# 6612.net
KiCad netlist of a schematic drawn in Altium Designer
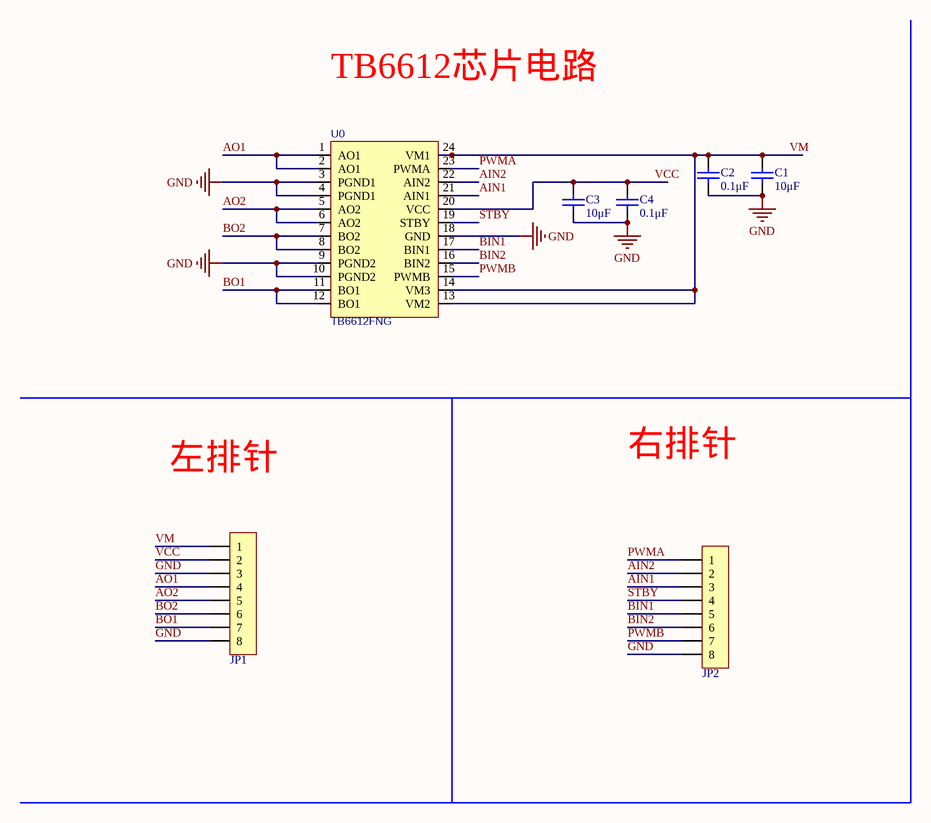
[diagram p0: 6612.SchDoc]

(export (version "E")
  (design (tool "Eeschema 10.0.6"))
  (components
    (comp (ref "C1")
      (value "10μF")
      (footprint "C0805_L")
      (description "贴片电容/MLCC电容")
      (libsource (lib "0.1 - 电阻-电容-电感-晶振-晶体-磁珠-电位器-法拉电容-馈通电容") (part "C"))
    )
    (comp (ref "C2")
      (value "0.1μF")
      (footprint "C0805_L")
      (description "贴片电容/MLCC电容")
      (libsource (lib "0.1 - 电阻-电容-电感-晶振-晶体-磁珠-电位器-法拉电容-馈通电容") (part "C"))
    )
    (comp (ref "C3")
      (value "10μF")
      (footprint "C0805_L")
      (description "贴片电容/MLCC电容")
      (libsource (lib "0.1 - 电阻-电容-电感-晶振-晶体-磁珠-电位器-法拉电容-馈通电容") (part "C"))
    )
    (comp (ref "C4")
      (value "0.1μF")
      (footprint "C0805_L")
      (description "贴片电容/MLCC电容")
      (libsource (lib "0.1 - 电阻-电容-电感-晶振-晶体-磁珠-电位器-法拉电容-馈通电容") (part "C"))
    )
    (comp (ref "JP1")
      (value "HDR-1X8")
      (footprint "HDR2.54-LI-8P")
      (description "8P接插件")
      (libsource (lib "5.5 - 2.54mm连接器(KF2EDGK_XH2.54_2.54排针排母)") (part "Header 8"))
    )
    (comp (ref "JP2")
      (value "HDR-1X8")
      (footprint "HDR2.54-LI-8P")
      (description "8P接插件")
      (libsource (lib "5.5 - 2.54mm连接器(KF2EDGK_XH2.54_2.54排针排母)") (part "Header 8"))
    )
    (comp (ref "U0")
      (value "TB6612FNG")
      (footprint "SSOP24_M")
      (description "电机驱动")
      (libsource (lib "0.8 - 常见芯片") (part "TB6612FNG"))
    )
  )
  (nets
    (net (code "1") (name "/AIN1") (class "Default")
      (node (ref "JP2") (pin "3") (pinfunction "3_3") (pintype "passive"))
      (node (ref "U0") (pin "21") (pinfunction "AIN1_21") (pintype "passive"))
    )
    (net (code "2") (name "/AIN2") (class "Default")
      (node (ref "JP2") (pin "2") (pinfunction "2_2") (pintype "passive"))
      (node (ref "U0") (pin "22") (pinfunction "AIN2_22") (pintype "passive"))
    )
    (net (code "3") (name "/AO1") (class "Default")
      (node (ref "JP1") (pin "4") (pinfunction "4_4") (pintype "passive"))
      (node (ref "U0") (pin "1") (pinfunction "AO1_1") (pintype "passive"))
      (node (ref "U0") (pin "2") (pinfunction "AO1_2") (pintype "passive"))
    )
    (net (code "4") (name "/AO2") (class "Default")
      (node (ref "JP1") (pin "5") (pinfunction "5_5") (pintype "passive"))
      (node (ref "U0") (pin "5") (pinfunction "AO2_5") (pintype "passive"))
      (node (ref "U0") (pin "6") (pinfunction "AO2_6") (pintype "passive"))
    )
    (net (code "5") (name "/BIN1") (class "Default")
      (node (ref "JP2") (pin "5") (pinfunction "5_5") (pintype "passive"))
      (node (ref "U0") (pin "17") (pinfunction "BIN1_17") (pintype "passive"))
    )
    (net (code "6") (name "/BIN2") (class "Default")
      (node (ref "JP2") (pin "6") (pinfunction "6_6") (pintype "passive"))
      (node (ref "U0") (pin "16") (pinfunction "BIN2_16") (pintype "passive"))
    )
    (net (code "7") (name "/BO1") (class "Default")
      (node (ref "JP1") (pin "7") (pinfunction "7_7") (pintype "passive"))
      (node (ref "U0") (pin "11") (pinfunction "BO1_11") (pintype "passive"))
      (node (ref "U0") (pin "12") (pinfunction "BO1_12") (pintype "passive"))
    )
    (net (code "8") (name "/BO2") (class "Default")
      (node (ref "JP1") (pin "6") (pinfunction "6_6") (pintype "passive"))
      (node (ref "U0") (pin "7") (pinfunction "BO2_7") (pintype "passive"))
      (node (ref "U0") (pin "8") (pinfunction "BO2_8") (pintype "passive"))
    )
    (net (code "9") (name "/PWMA") (class "Default")
      (node (ref "JP2") (pin "1") (pinfunction "1_1") (pintype "passive"))
      (node (ref "U0") (pin "23") (pinfunction "PWMA_23") (pintype "passive"))
    )
    (net (code "10") (name "/PWMB") (class "Default")
      (node (ref "JP2") (pin "7") (pinfunction "7_7") (pintype "passive"))
      (node (ref "U0") (pin "15") (pinfunction "PWMB_15") (pintype "passive"))
    )
    (net (code "11") (name "/STBY") (class "Default")
      (node (ref "JP2") (pin "4") (pinfunction "4_4") (pintype "passive"))
      (node (ref "U0") (pin "19") (pinfunction "STBY_19") (pintype "passive"))
    )
    (net (code "12") (name "/VCC") (class "Default")
      (node (ref "C3") (pin "2") (pinfunction "2_2") (pintype "passive"))
      (node (ref "C4") (pin "2") (pinfunction "2_2") (pintype "passive"))
      (node (ref "JP1") (pin "2") (pinfunction "2_2") (pintype "passive"))
      (node (ref "U0") (pin "20") (pinfunction "VCC_20") (pintype "passive"))
    )
    (net (code "13") (name "/VM") (class "Default")
      (node (ref "C1") (pin "2") (pinfunction "2_2") (pintype "passive"))
      (node (ref "C2") (pin "2") (pinfunction "2_2") (pintype "passive"))
      (node (ref "JP1") (pin "1") (pinfunction "1_1") (pintype "passive"))
      (node (ref "U0") (pin "13") (pinfunction "VM2_13") (pintype "passive"))
      (node (ref "U0") (pin "14") (pinfunction "VM3_14") (pintype "passive"))
      (node (ref "U0") (pin "24") (pinfunction "VM1_24") (pintype "passive"))
    )
    (net (code "14") (name "GND") (class "Default")
      (node (ref "C1") (pin "1") (pinfunction "1_1") (pintype "passive"))
      (node (ref "C2") (pin "1") (pinfunction "1_1") (pintype "passive"))
      (node (ref "C3") (pin "1") (pinfunction "1_1") (pintype "passive"))
      (node (ref "C4") (pin "1") (pinfunction "1_1") (pintype "passive"))
      (node (ref "JP1") (pin "3") (pinfunction "3_3") (pintype "passive"))
      (node (ref "JP1") (pin "8") (pinfunction "8_8") (pintype "passive"))
      (node (ref "JP2") (pin "8") (pinfunction "8_8") (pintype "passive"))
      (node (ref "U0") (pin "10") (pinfunction "PGND2_10") (pintype "passive"))
      (node (ref "U0") (pin "18") (pinfunction "GND_18") (pintype "passive"))
      (node (ref "U0") (pin "3") (pinfunction "PGND1_3") (pintype "passive"))
      (node (ref "U0") (pin "4") (pinfunction "PGND1_4") (pintype "passive"))
      (node (ref "U0") (pin "9") (pinfunction "PGND2_9") (pintype "passive"))
    )
  )
)
